# untitled.net
KiCad netlist of a schematic drawn in EAGLE
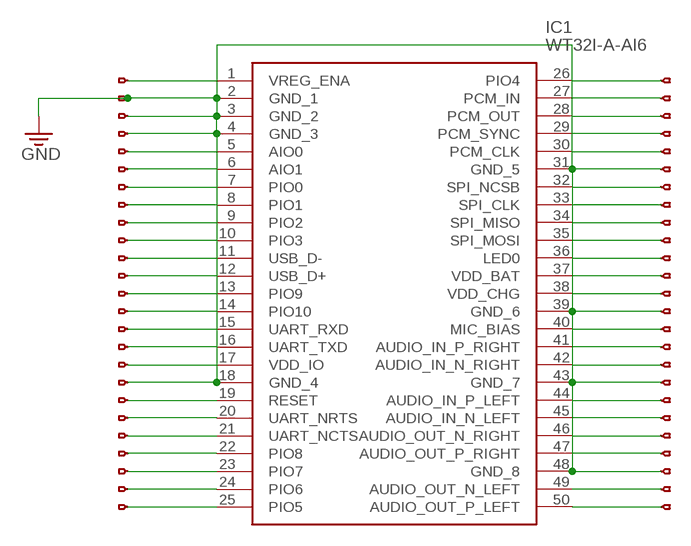
[diagram p0: schematic, sheet 1]

(export (version "E")
  (design (tool "Eeschema 10.0.6"))
  (components
    (comp (ref "IC1")
      (value "WT32I-A-AI6")
      (footprint "eagle-import:WT32I-A-AI6")
      (fields
        (field (name "MANUFACTURER_PART_NUMBER") "WT32i-A-AI6")
        (field (name "MOUSER_PART_NUMBER") "603-WT32I-A-AI6")
      )
      (libsource (lib "eagle-import") (part "WT32I-A-AI6"))
    )
    (comp (ref "JP1")
      (value "HEADERHOLE-HEADERHOLE")
      (footprint "eagle-import:1X1-HEADER-HOLE")
      (libsource (lib "eagle-import") (part "HEADERHOLE-HEADERHOLE"))
    )
    (comp (ref "JP2")
      (value "HEADERHOLE-HEADERHOLE")
      (footprint "eagle-import:1X1-HEADER-HOLE")
      (libsource (lib "eagle-import") (part "HEADERHOLE-HEADERHOLE"))
    )
    (comp (ref "JP3")
      (value "HEADERHOLE-HEADERHOLE")
      (footprint "eagle-import:1X1-HEADER-HOLE")
      (libsource (lib "eagle-import") (part "HEADERHOLE-HEADERHOLE"))
    )
    (comp (ref "JP4")
      (value "HEADERHOLE-HEADERHOLE")
      (footprint "eagle-import:1X1-HEADER-HOLE")
      (libsource (lib "eagle-import") (part "HEADERHOLE-HEADERHOLE"))
    )
    (comp (ref "JP5")
      (value "HEADERHOLE-HEADERHOLE")
      (footprint "eagle-import:1X1-HEADER-HOLE")
      (libsource (lib "eagle-import") (part "HEADERHOLE-HEADERHOLE"))
    )
    (comp (ref "JP6")
      (value "HEADERHOLE-HEADERHOLE")
      (footprint "eagle-import:1X1-HEADER-HOLE")
      (libsource (lib "eagle-import") (part "HEADERHOLE-HEADERHOLE"))
    )
    (comp (ref "JP7")
      (value "HEADERHOLE-HEADERHOLE")
      (footprint "eagle-import:1X1-HEADER-HOLE")
      (libsource (lib "eagle-import") (part "HEADERHOLE-HEADERHOLE"))
    )
    (comp (ref "JP8")
      (value "HEADERHOLE-HEADERHOLE")
      (footprint "eagle-import:1X1-HEADER-HOLE")
      (libsource (lib "eagle-import") (part "HEADERHOLE-HEADERHOLE"))
    )
    (comp (ref "JP9")
      (value "HEADERHOLE-HEADERHOLE")
      (footprint "eagle-import:1X1-HEADER-HOLE")
      (libsource (lib "eagle-import") (part "HEADERHOLE-HEADERHOLE"))
    )
    (comp (ref "JP10")
      (value "HEADERHOLE-HEADERHOLE")
      (footprint "eagle-import:1X1-HEADER-HOLE")
      (libsource (lib "eagle-import") (part "HEADERHOLE-HEADERHOLE"))
    )
    (comp (ref "JP11")
      (value "HEADERHOLE-HEADERHOLE")
      (footprint "eagle-import:1X1-HEADER-HOLE")
      (libsource (lib "eagle-import") (part "HEADERHOLE-HEADERHOLE"))
    )
    (comp (ref "JP12")
      (value "HEADERHOLE-HEADERHOLE")
      (footprint "eagle-import:1X1-HEADER-HOLE")
      (libsource (lib "eagle-import") (part "HEADERHOLE-HEADERHOLE"))
    )
    (comp (ref "JP13")
      (value "HEADERHOLE-HEADERHOLE")
      (footprint "eagle-import:1X1-HEADER-HOLE")
      (libsource (lib "eagle-import") (part "HEADERHOLE-HEADERHOLE"))
    )
    (comp (ref "JP14")
      (value "HEADERHOLE-HEADERHOLE")
      (footprint "eagle-import:1X1-HEADER-HOLE")
      (libsource (lib "eagle-import") (part "HEADERHOLE-HEADERHOLE"))
    )
    (comp (ref "JP15")
      (value "HEADERHOLE-HEADERHOLE")
      (footprint "eagle-import:1X1-HEADER-HOLE")
      (libsource (lib "eagle-import") (part "HEADERHOLE-HEADERHOLE"))
    )
    (comp (ref "JP16")
      (value "HEADERHOLE-HEADERHOLE")
      (footprint "eagle-import:1X1-HEADER-HOLE")
      (libsource (lib "eagle-import") (part "HEADERHOLE-HEADERHOLE"))
    )
    (comp (ref "JP17")
      (value "HEADERHOLE-HEADERHOLE")
      (footprint "eagle-import:1X1-HEADER-HOLE")
      (libsource (lib "eagle-import") (part "HEADERHOLE-HEADERHOLE"))
    )
    (comp (ref "JP18")
      (value "HEADERHOLE-HEADERHOLE")
      (footprint "eagle-import:1X1-HEADER-HOLE")
      (libsource (lib "eagle-import") (part "HEADERHOLE-HEADERHOLE"))
    )
    (comp (ref "JP19")
      (value "HEADERHOLE-HEADERHOLE")
      (footprint "eagle-import:1X1-HEADER-HOLE")
      (libsource (lib "eagle-import") (part "HEADERHOLE-HEADERHOLE"))
    )
    (comp (ref "JP20")
      (value "HEADERHOLE-HEADERHOLE")
      (footprint "eagle-import:1X1-HEADER-HOLE")
      (libsource (lib "eagle-import") (part "HEADERHOLE-HEADERHOLE"))
    )
    (comp (ref "JP21")
      (value "HEADERHOLE-HEADERHOLE")
      (footprint "eagle-import:1X1-HEADER-HOLE")
      (libsource (lib "eagle-import") (part "HEADERHOLE-HEADERHOLE"))
    )
    (comp (ref "JP22")
      (value "HEADERHOLE-HEADERHOLE")
      (footprint "eagle-import:1X1-HEADER-HOLE")
      (libsource (lib "eagle-import") (part "HEADERHOLE-HEADERHOLE"))
    )
    (comp (ref "JP23")
      (value "HEADERHOLE-HEADERHOLE")
      (footprint "eagle-import:1X1-HEADER-HOLE")
      (libsource (lib "eagle-import") (part "HEADERHOLE-HEADERHOLE"))
    )
    (comp (ref "JP24")
      (value "HEADERHOLE-HEADERHOLE")
      (footprint "eagle-import:1X1-HEADER-HOLE")
      (libsource (lib "eagle-import") (part "HEADERHOLE-HEADERHOLE"))
    )
    (comp (ref "JP25")
      (value "HEADERHOLE-HEADERHOLE")
      (footprint "eagle-import:1X1-HEADER-HOLE")
      (libsource (lib "eagle-import") (part "HEADERHOLE-HEADERHOLE"))
    )
    (comp (ref "JP26")
      (value "HEADERHOLE-HEADERHOLE")
      (footprint "eagle-import:1X1-HEADER-HOLE")
      (libsource (lib "eagle-import") (part "HEADERHOLE-HEADERHOLE"))
    )
    (comp (ref "JP27")
      (value "HEADERHOLE-HEADERHOLE")
      (footprint "eagle-import:1X1-HEADER-HOLE")
      (libsource (lib "eagle-import") (part "HEADERHOLE-HEADERHOLE"))
    )
    (comp (ref "JP28")
      (value "HEADERHOLE-HEADERHOLE")
      (footprint "eagle-import:1X1-HEADER-HOLE")
      (libsource (lib "eagle-import") (part "HEADERHOLE-HEADERHOLE"))
    )
    (comp (ref "JP29")
      (value "HEADERHOLE-HEADERHOLE")
      (footprint "eagle-import:1X1-HEADER-HOLE")
      (libsource (lib "eagle-import") (part "HEADERHOLE-HEADERHOLE"))
    )
    (comp (ref "JP30")
      (value "HEADERHOLE-HEADERHOLE")
      (footprint "eagle-import:1X1-HEADER-HOLE")
      (libsource (lib "eagle-import") (part "HEADERHOLE-HEADERHOLE"))
    )
    (comp (ref "JP31")
      (value "HEADERHOLE-HEADERHOLE")
      (footprint "eagle-import:1X1-HEADER-HOLE")
      (libsource (lib "eagle-import") (part "HEADERHOLE-HEADERHOLE"))
    )
    (comp (ref "JP32")
      (value "HEADERHOLE-HEADERHOLE")
      (footprint "eagle-import:1X1-HEADER-HOLE")
      (libsource (lib "eagle-import") (part "HEADERHOLE-HEADERHOLE"))
    )
    (comp (ref "JP33")
      (value "HEADERHOLE-HEADERHOLE")
      (footprint "eagle-import:1X1-HEADER-HOLE")
      (libsource (lib "eagle-import") (part "HEADERHOLE-HEADERHOLE"))
    )
    (comp (ref "JP34")
      (value "HEADERHOLE-HEADERHOLE")
      (footprint "eagle-import:1X1-HEADER-HOLE")
      (libsource (lib "eagle-import") (part "HEADERHOLE-HEADERHOLE"))
    )
    (comp (ref "JP35")
      (value "HEADERHOLE-HEADERHOLE")
      (footprint "eagle-import:1X1-HEADER-HOLE")
      (libsource (lib "eagle-import") (part "HEADERHOLE-HEADERHOLE"))
    )
    (comp (ref "JP36")
      (value "HEADERHOLE-HEADERHOLE")
      (footprint "eagle-import:1X1-HEADER-HOLE")
      (libsource (lib "eagle-import") (part "HEADERHOLE-HEADERHOLE"))
    )
    (comp (ref "JP37")
      (value "HEADERHOLE-HEADERHOLE")
      (footprint "eagle-import:1X1-HEADER-HOLE")
      (libsource (lib "eagle-import") (part "HEADERHOLE-HEADERHOLE"))
    )
    (comp (ref "JP38")
      (value "HEADERHOLE-HEADERHOLE")
      (footprint "eagle-import:1X1-HEADER-HOLE")
      (libsource (lib "eagle-import") (part "HEADERHOLE-HEADERHOLE"))
    )
    (comp (ref "JP39")
      (value "HEADERHOLE-HEADERHOLE")
      (footprint "eagle-import:1X1-HEADER-HOLE")
      (libsource (lib "eagle-import") (part "HEADERHOLE-HEADERHOLE"))
    )
    (comp (ref "JP40")
      (value "HEADERHOLE-HEADERHOLE")
      (footprint "eagle-import:1X1-HEADER-HOLE")
      (libsource (lib "eagle-import") (part "HEADERHOLE-HEADERHOLE"))
    )
    (comp (ref "JP41")
      (value "HEADERHOLE-HEADERHOLE")
      (footprint "eagle-import:1X1-HEADER-HOLE")
      (libsource (lib "eagle-import") (part "HEADERHOLE-HEADERHOLE"))
    )
    (comp (ref "JP42")
      (value "HEADERHOLE-HEADERHOLE")
      (footprint "eagle-import:1X1-HEADER-HOLE")
      (libsource (lib "eagle-import") (part "HEADERHOLE-HEADERHOLE"))
    )
    (comp (ref "JP43")
      (value "HEADERHOLE-HEADERHOLE")
      (footprint "eagle-import:1X1-HEADER-HOLE")
      (libsource (lib "eagle-import") (part "HEADERHOLE-HEADERHOLE"))
    )
    (comp (ref "JP44")
      (value "HEADERHOLE-HEADERHOLE")
      (footprint "eagle-import:1X1-HEADER-HOLE")
      (libsource (lib "eagle-import") (part "HEADERHOLE-HEADERHOLE"))
    )
    (comp (ref "JP45")
      (value "HEADERHOLE-HEADERHOLE")
      (footprint "eagle-import:1X1-HEADER-HOLE")
      (libsource (lib "eagle-import") (part "HEADERHOLE-HEADERHOLE"))
    )
    (comp (ref "JP46")
      (value "HEADERHOLE-HEADERHOLE")
      (footprint "eagle-import:1X1-HEADER-HOLE")
      (libsource (lib "eagle-import") (part "HEADERHOLE-HEADERHOLE"))
    )
    (comp (ref "JP47")
      (value "HEADERHOLE-HEADERHOLE")
      (footprint "eagle-import:1X1-HEADER-HOLE")
      (libsource (lib "eagle-import") (part "HEADERHOLE-HEADERHOLE"))
    )
    (comp (ref "JP48")
      (value "HEADERHOLE-HEADERHOLE")
      (footprint "eagle-import:1X1-HEADER-HOLE")
      (libsource (lib "eagle-import") (part "HEADERHOLE-HEADERHOLE"))
    )
    (comp (ref "JP49")
      (value "HEADERHOLE-HEADERHOLE")
      (footprint "eagle-import:1X1-HEADER-HOLE")
      (libsource (lib "eagle-import") (part "HEADERHOLE-HEADERHOLE"))
    )
    (comp (ref "JP50")
      (value "HEADERHOLE-HEADERHOLE")
      (footprint "eagle-import:1X1-HEADER-HOLE")
      (libsource (lib "eagle-import") (part "HEADERHOLE-HEADERHOLE"))
    )
  )
  (nets
    (net (code "1") (name "GND") (class "Default")
      (node (ref "IC1") (pin "18") (pinfunction "GND_4_18") (pintype "bidirectional"))
      (node (ref "IC1") (pin "2") (pinfunction "GND_1_2") (pintype "bidirectional"))
      (node (ref "IC1") (pin "3") (pinfunction "GND_2_3") (pintype "bidirectional"))
      (node (ref "IC1") (pin "31") (pinfunction "GND_5_31") (pintype "bidirectional"))
      (node (ref "IC1") (pin "39") (pinfunction "GND_6_39") (pintype "bidirectional"))
      (node (ref "IC1") (pin "4") (pinfunction "GND_3_4") (pintype "bidirectional"))
      (node (ref "IC1") (pin "43") (pinfunction "GND_7_43") (pintype "bidirectional"))
      (node (ref "IC1") (pin "48") (pinfunction "GND_8_48") (pintype "bidirectional"))
      (node (ref "JP18") (pin "1") (pinfunction "P$1_1") (pintype "bidirectional"))
      (node (ref "JP2") (pin "1") (pinfunction "P$1_1") (pintype "bidirectional"))
      (node (ref "JP3") (pin "1") (pinfunction "P$1_1") (pintype "bidirectional"))
      (node (ref "JP31") (pin "1") (pinfunction "P$1_1") (pintype "bidirectional"))
      (node (ref "JP39") (pin "1") (pinfunction "P$1_1") (pintype "bidirectional"))
      (node (ref "JP4") (pin "1") (pinfunction "P$1_1") (pintype "bidirectional"))
      (node (ref "JP43") (pin "1") (pinfunction "P$1_1") (pintype "bidirectional"))
      (node (ref "JP48") (pin "1") (pinfunction "P$1_1") (pintype "bidirectional"))
    )
    (net (code "2") (name "Net-(IC1-AIO0)") (class "Default")
      (node (ref "IC1") (pin "5") (pinfunction "AIO0_5") (pintype "bidirectional"))
      (node (ref "JP5") (pin "1") (pinfunction "P$1_1") (pintype "bidirectional"))
    )
    (net (code "3") (name "Net-(IC1-AIO1)") (class "Default")
      (node (ref "IC1") (pin "6") (pinfunction "AIO1_6") (pintype "bidirectional"))
      (node (ref "JP6") (pin "1") (pinfunction "P$1_1") (pintype "bidirectional"))
    )
    (net (code "4") (name "Net-(IC1-AUDIO_IN_N_LEFT)") (class "Default")
      (node (ref "IC1") (pin "45") (pinfunction "AUDIO_IN_N_LEFT_45") (pintype "bidirectional"))
      (node (ref "JP45") (pin "1") (pinfunction "P$1_1") (pintype "bidirectional"))
    )
    (net (code "5") (name "Net-(IC1-AUDIO_IN_N_RIGHT)") (class "Default")
      (node (ref "IC1") (pin "42") (pinfunction "AUDIO_IN_N_RIGHT_42") (pintype "bidirectional"))
      (node (ref "JP42") (pin "1") (pinfunction "P$1_1") (pintype "bidirectional"))
    )
    (net (code "6") (name "Net-(IC1-AUDIO_IN_P_LEFT)") (class "Default")
      (node (ref "IC1") (pin "44") (pinfunction "AUDIO_IN_P_LEFT_44") (pintype "bidirectional"))
      (node (ref "JP44") (pin "1") (pinfunction "P$1_1") (pintype "bidirectional"))
    )
    (net (code "7") (name "Net-(IC1-AUDIO_IN_P_RIGHT)") (class "Default")
      (node (ref "IC1") (pin "41") (pinfunction "AUDIO_IN_P_RIGHT_41") (pintype "bidirectional"))
      (node (ref "JP41") (pin "1") (pinfunction "P$1_1") (pintype "bidirectional"))
    )
    (net (code "8") (name "Net-(IC1-AUDIO_OUT_N_LEFT)") (class "Default")
      (node (ref "IC1") (pin "49") (pinfunction "AUDIO_OUT_N_LEFT_49") (pintype "bidirectional"))
      (node (ref "JP49") (pin "1") (pinfunction "P$1_1") (pintype "bidirectional"))
    )
    (net (code "9") (name "Net-(IC1-AUDIO_OUT_N_RIGHT)") (class "Default")
      (node (ref "IC1") (pin "46") (pinfunction "AUDIO_OUT_N_RIGHT_46") (pintype "bidirectional"))
      (node (ref "JP46") (pin "1") (pinfunction "P$1_1") (pintype "bidirectional"))
    )
    (net (code "10") (name "Net-(IC1-AUDIO_OUT_P_LEFT)") (class "Default")
      (node (ref "IC1") (pin "50") (pinfunction "AUDIO_OUT_P_LEFT_50") (pintype "bidirectional"))
      (node (ref "JP50") (pin "1") (pinfunction "P$1_1") (pintype "bidirectional"))
    )
    (net (code "11") (name "Net-(IC1-AUDIO_OUT_P_RIGHT)") (class "Default")
      (node (ref "IC1") (pin "47") (pinfunction "AUDIO_OUT_P_RIGHT_47") (pintype "bidirectional"))
      (node (ref "JP47") (pin "1") (pinfunction "P$1_1") (pintype "bidirectional"))
    )
    (net (code "12") (name "Net-(IC1-LED0)") (class "Default")
      (node (ref "IC1") (pin "36") (pinfunction "LED0_36") (pintype "bidirectional"))
      (node (ref "JP36") (pin "1") (pinfunction "P$1_1") (pintype "bidirectional"))
    )
    (net (code "13") (name "Net-(IC1-MIC_BIAS)") (class "Default")
      (node (ref "IC1") (pin "40") (pinfunction "MIC_BIAS_40") (pintype "bidirectional"))
      (node (ref "JP40") (pin "1") (pinfunction "P$1_1") (pintype "bidirectional"))
    )
    (net (code "14") (name "Net-(IC1-PCM_CLK)") (class "Default")
      (node (ref "IC1") (pin "30") (pinfunction "PCM_CLK_30") (pintype "bidirectional"))
      (node (ref "JP30") (pin "1") (pinfunction "P$1_1") (pintype "bidirectional"))
    )
    (net (code "15") (name "Net-(IC1-PCM_IN)") (class "Default")
      (node (ref "IC1") (pin "27") (pinfunction "PCM_IN_27") (pintype "bidirectional"))
      (node (ref "JP27") (pin "1") (pinfunction "P$1_1") (pintype "bidirectional"))
    )
    (net (code "16") (name "Net-(IC1-PCM_OUT)") (class "Default")
      (node (ref "IC1") (pin "28") (pinfunction "PCM_OUT_28") (pintype "bidirectional"))
      (node (ref "JP28") (pin "1") (pinfunction "P$1_1") (pintype "bidirectional"))
    )
    (net (code "17") (name "Net-(IC1-PCM_SYNC)") (class "Default")
      (node (ref "IC1") (pin "29") (pinfunction "PCM_SYNC_29") (pintype "bidirectional"))
      (node (ref "JP29") (pin "1") (pinfunction "P$1_1") (pintype "bidirectional"))
    )
    (net (code "18") (name "Net-(IC1-PIO0)") (class "Default")
      (node (ref "IC1") (pin "7") (pinfunction "PIO0_7") (pintype "bidirectional"))
      (node (ref "JP7") (pin "1") (pinfunction "P$1_1") (pintype "bidirectional"))
    )
    (net (code "19") (name "Net-(IC1-PIO1)") (class "Default")
      (node (ref "IC1") (pin "8") (pinfunction "PIO1_8") (pintype "bidirectional"))
      (node (ref "JP8") (pin "1") (pinfunction "P$1_1") (pintype "bidirectional"))
    )
    (net (code "20") (name "Net-(IC1-PIO2)") (class "Default")
      (node (ref "IC1") (pin "9") (pinfunction "PIO2_9") (pintype "bidirectional"))
      (node (ref "JP9") (pin "1") (pinfunction "P$1_1") (pintype "bidirectional"))
    )
    (net (code "21") (name "Net-(IC1-PIO3)") (class "Default")
      (node (ref "IC1") (pin "10") (pinfunction "PIO3_10") (pintype "bidirectional"))
      (node (ref "JP10") (pin "1") (pinfunction "P$1_1") (pintype "bidirectional"))
    )
    (net (code "22") (name "Net-(IC1-PIO4)") (class "Default")
      (node (ref "IC1") (pin "26") (pinfunction "PIO4_26") (pintype "bidirectional"))
      (node (ref "JP26") (pin "1") (pinfunction "P$1_1") (pintype "bidirectional"))
    )
    (net (code "23") (name "Net-(IC1-PIO5)") (class "Default")
      (node (ref "IC1") (pin "25") (pinfunction "PIO5_25") (pintype "bidirectional"))
      (node (ref "JP25") (pin "1") (pinfunction "P$1_1") (pintype "bidirectional"))
    )
    (net (code "24") (name "Net-(IC1-PIO6)") (class "Default")
      (node (ref "IC1") (pin "24") (pinfunction "PIO6_24") (pintype "bidirectional"))
      (node (ref "JP24") (pin "1") (pinfunction "P$1_1") (pintype "bidirectional"))
    )
    (net (code "25") (name "Net-(IC1-PIO7)") (class "Default")
      (node (ref "IC1") (pin "23") (pinfunction "PIO7_23") (pintype "bidirectional"))
      (node (ref "JP23") (pin "1") (pinfunction "P$1_1") (pintype "bidirectional"))
    )
    (net (code "26") (name "Net-(IC1-PIO8)") (class "Default")
      (node (ref "IC1") (pin "22") (pinfunction "PIO8_22") (pintype "bidirectional"))
      (node (ref "JP22") (pin "1") (pinfunction "P$1_1") (pintype "bidirectional"))
    )
    (net (code "27") (name "Net-(IC1-PIO9)") (class "Default")
      (node (ref "IC1") (pin "13") (pinfunction "PIO9_13") (pintype "bidirectional"))
      (node (ref "JP13") (pin "1") (pinfunction "P$1_1") (pintype "bidirectional"))
    )
    (net (code "28") (name "Net-(IC1-PIO10)") (class "Default")
      (node (ref "IC1") (pin "14") (pinfunction "PIO10_14") (pintype "bidirectional"))
      (node (ref "JP14") (pin "1") (pinfunction "P$1_1") (pintype "bidirectional"))
    )
    (net (code "29") (name "Net-(IC1-RESET)") (class "Default")
      (node (ref "IC1") (pin "19") (pinfunction "RESET_19") (pintype "bidirectional"))
      (node (ref "JP19") (pin "1") (pinfunction "P$1_1") (pintype "bidirectional"))
    )
    (net (code "30") (name "Net-(IC1-SPI_CLK)") (class "Default")
      (node (ref "IC1") (pin "33") (pinfunction "SPI_CLK_33") (pintype "bidirectional"))
      (node (ref "JP33") (pin "1") (pinfunction "P$1_1") (pintype "bidirectional"))
    )
    (net (code "31") (name "Net-(IC1-SPI_MISO)") (class "Default")
      (node (ref "IC1") (pin "34") (pinfunction "SPI_MISO_34") (pintype "bidirectional"))
      (node (ref "JP34") (pin "1") (pinfunction "P$1_1") (pintype "bidirectional"))
    )
    (net (code "32") (name "Net-(IC1-SPI_MOSI)") (class "Default")
      (node (ref "IC1") (pin "35") (pinfunction "SPI_MOSI_35") (pintype "bidirectional"))
      (node (ref "JP35") (pin "1") (pinfunction "P$1_1") (pintype "bidirectional"))
    )
    (net (code "33") (name "Net-(IC1-SPI_NCSB)") (class "Default")
      (node (ref "IC1") (pin "32") (pinfunction "SPI_NCSB_32") (pintype "bidirectional"))
      (node (ref "JP32") (pin "1") (pinfunction "P$1_1") (pintype "bidirectional"))
    )
    (net (code "34") (name "Net-(IC1-UART_NCTS)") (class "Default")
      (node (ref "IC1") (pin "21") (pinfunction "UART_NCTS_21") (pintype "bidirectional"))
      (node (ref "JP21") (pin "1") (pinfunction "P$1_1") (pintype "bidirectional"))
    )
    (net (code "35") (name "Net-(IC1-UART_NRTS)") (class "Default")
      (node (ref "IC1") (pin "20") (pinfunction "UART_NRTS_20") (pintype "bidirectional"))
      (node (ref "JP20") (pin "1") (pinfunction "P$1_1") (pintype "bidirectional"))
    )
    (net (code "36") (name "Net-(IC1-UART_RXD)") (class "Default")
      (node (ref "IC1") (pin "15") (pinfunction "UART_RXD_15") (pintype "bidirectional"))
      (node (ref "JP15") (pin "1") (pinfunction "P$1_1") (pintype "bidirectional"))
    )
    (net (code "37") (name "Net-(IC1-UART_TXD)") (class "Default")
      (node (ref "IC1") (pin "16") (pinfunction "UART_TXD_16") (pintype "bidirectional"))
      (node (ref "JP16") (pin "1") (pinfunction "P$1_1") (pintype "bidirectional"))
    )
    (net (code "38") (name "Net-(IC1-USB_D+)") (class "Default")
      (node (ref "IC1") (pin "12") (pinfunction "USB_D+_12") (pintype "bidirectional"))
      (node (ref "JP12") (pin "1") (pinfunction "P$1_1") (pintype "bidirectional"))
    )
    (net (code "39") (name "Net-(IC1-USB_D-)") (class "Default")
      (node (ref "IC1") (pin "11") (pinfunction "USB_D-_11") (pintype "bidirectional"))
      (node (ref "JP11") (pin "1") (pinfunction "P$1_1") (pintype "bidirectional"))
    )
    (net (code "40") (name "Net-(IC1-VDD_BAT)") (class "Default")
      (node (ref "IC1") (pin "37") (pinfunction "VDD_BAT_37") (pintype "bidirectional"))
      (node (ref "JP37") (pin "1") (pinfunction "P$1_1") (pintype "bidirectional"))
    )
    (net (code "41") (name "Net-(IC1-VDD_CHG)") (class "Default")
      (node (ref "IC1") (pin "38") (pinfunction "VDD_CHG_38") (pintype "bidirectional"))
      (node (ref "JP38") (pin "1") (pinfunction "P$1_1") (pintype "bidirectional"))
    )
    (net (code "42") (name "Net-(IC1-VDD_IO)") (class "Default")
      (node (ref "IC1") (pin "17") (pinfunction "VDD_IO_17") (pintype "bidirectional"))
      (node (ref "JP17") (pin "1") (pinfunction "P$1_1") (pintype "bidirectional"))
    )
    (net (code "43") (name "Net-(IC1-VREG_ENA)") (class "Default")
      (node (ref "IC1") (pin "1") (pinfunction "VREG_ENA_1") (pintype "bidirectional"))
      (node (ref "JP1") (pin "1") (pinfunction "P$1_1") (pintype "bidirectional"))
    )
  )
)
